# ui_ux.net
KiCad netlist of a schematic drawn in Altium Designer
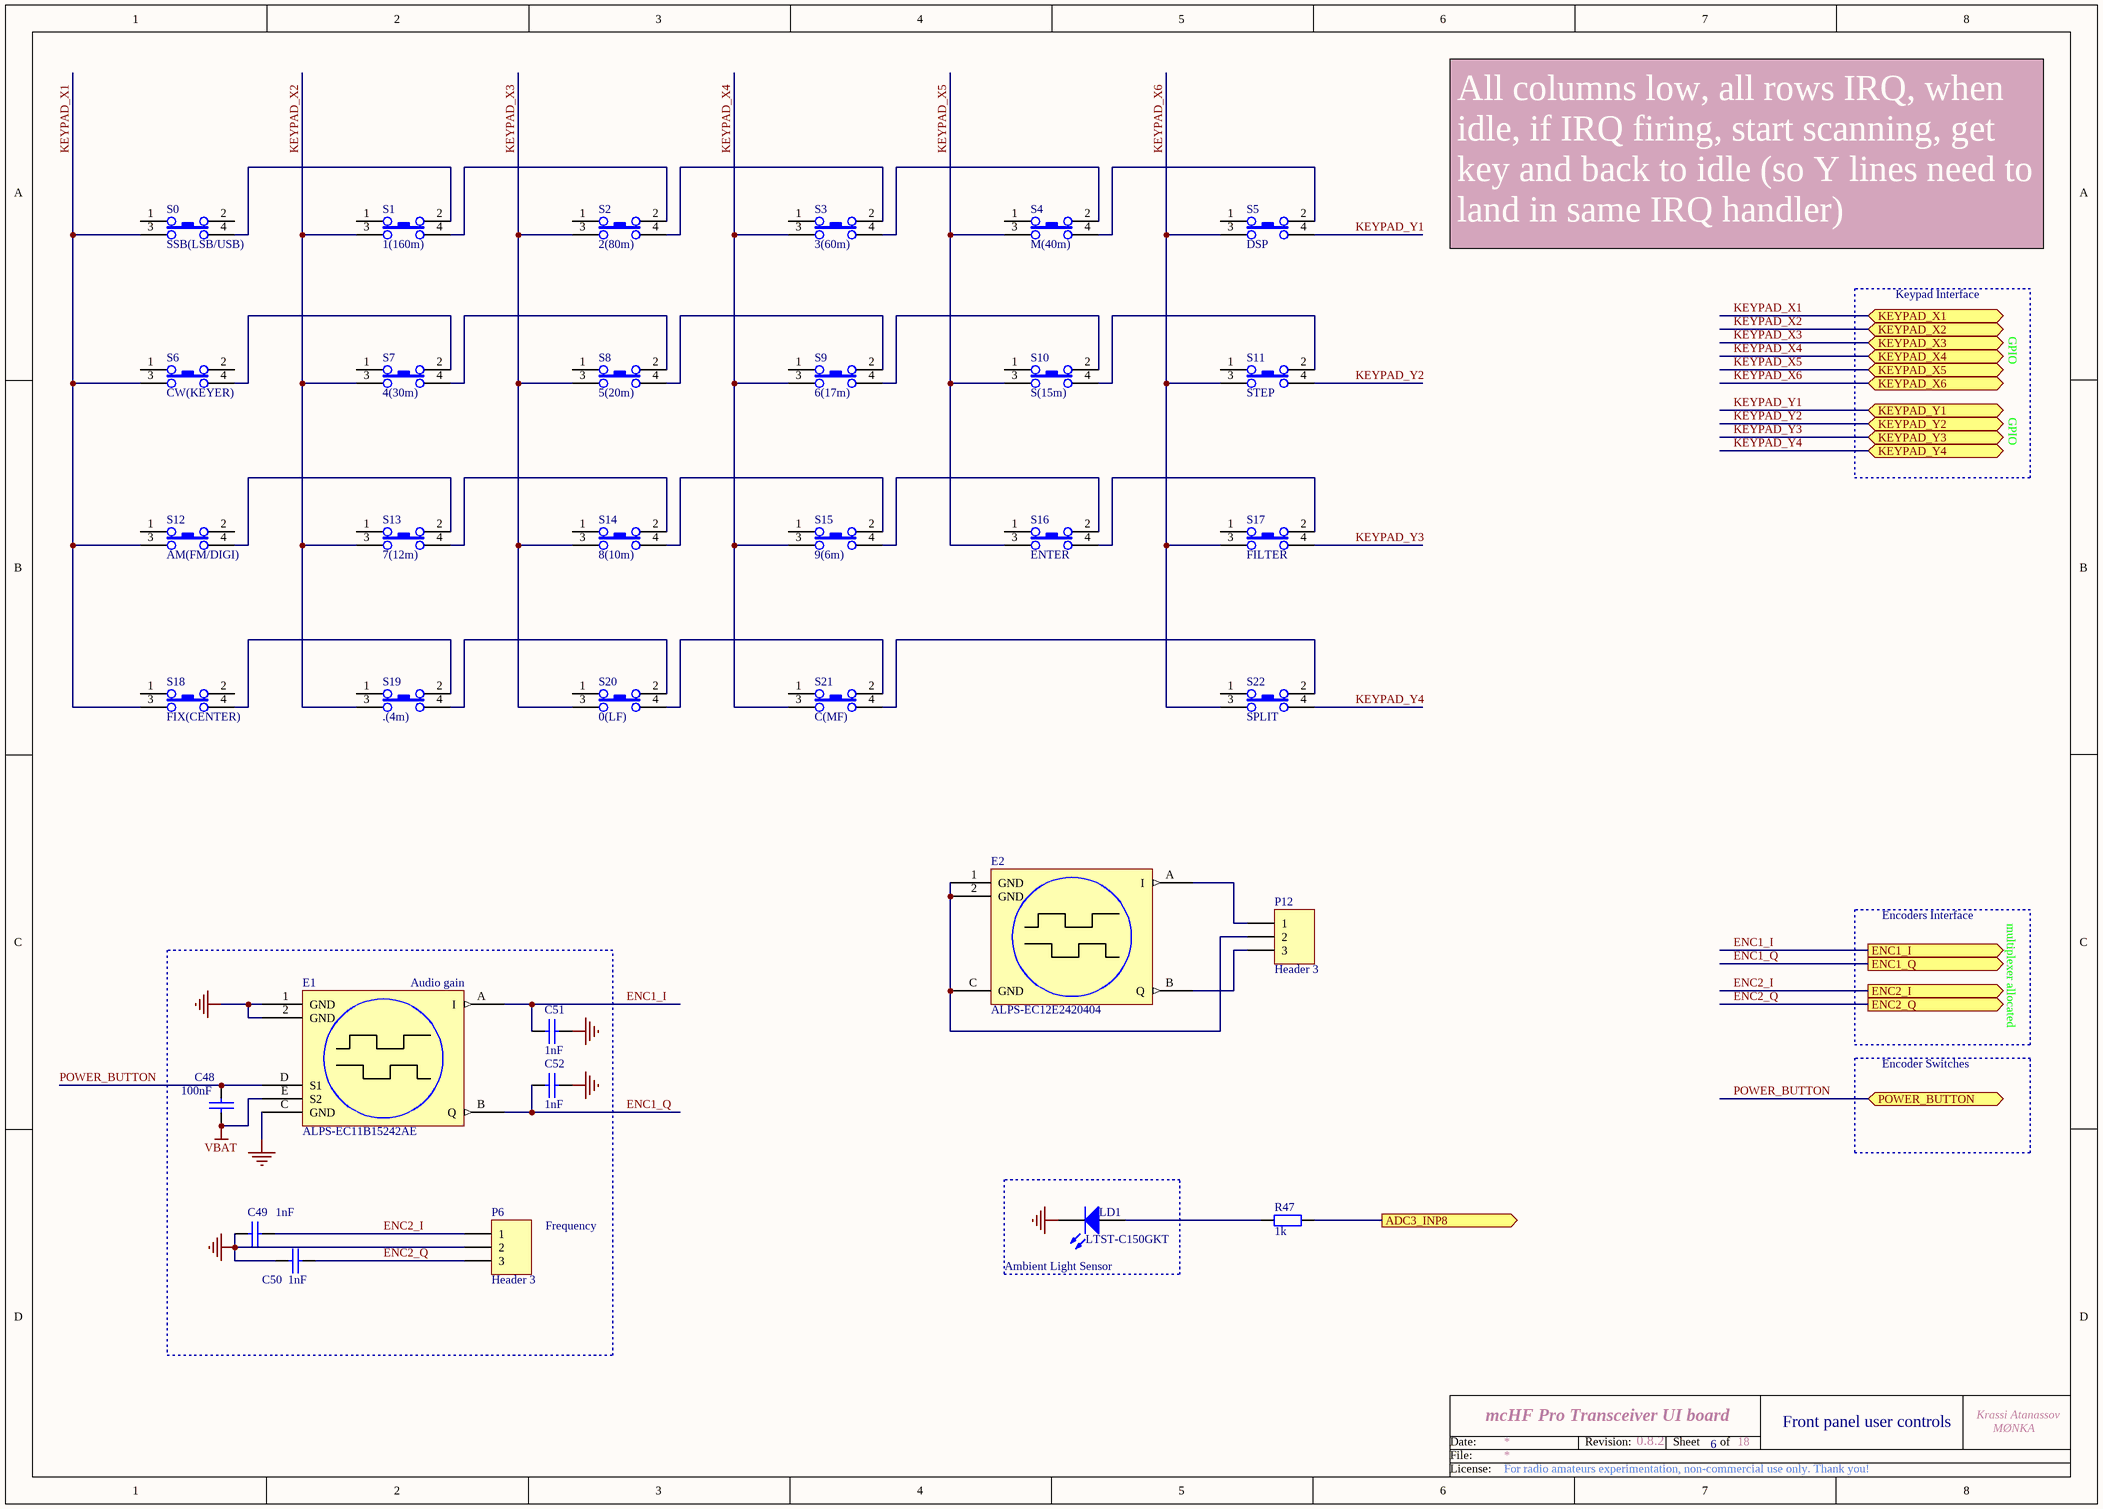
[diagram p0: ui_ux.SchDoc]

(export (version "E")
  (design (tool "Eeschema 10.0.6"))
  (components
    (comp (ref "C48")
      (value "100nF")
      (footprint "0805")
      (description "Capacitor")
      (libsource (lib "mcHF_ui") (part "CAP"))
    )
    (comp (ref "C49")
      (value "1nF")
      (footprint "0805")
      (description "Capacitor")
      (libsource (lib "mcHF_ui") (part "CAP"))
    )
    (comp (ref "C50")
      (value "1nF")
      (footprint "0805")
      (description "Capacitor")
      (libsource (lib "mcHF_ui") (part "CAP"))
    )
    (comp (ref "C51")
      (value "1nF")
      (footprint "0805")
      (description "Capacitor")
      (libsource (lib "mcHF_ui") (part "CAP"))
    )
    (comp (ref "C52")
      (value "1nF")
      (footprint "0805")
      (description "Capacitor")
      (libsource (lib "mcHF_ui") (part "CAP"))
    )
    (comp (ref "E1")
      (value "ALPS-EC11B15242AE")
      (footprint "EC11B_Horiz")
      (description "Horizontal Encoder")
      (libsource (lib "__ui") (part "EC11B_H"))
    )
    (comp (ref "E2")
      (value "ALPS-EC12E2420404")
      (footprint "Encoder")
      (description "ALPS Rotary Encoder")
      (libsource (lib "__ui") (part "Encoder"))
    )
    (comp (ref "LD1")
      (value "LTST-C150GKT")
      (footprint "1206_Elec_Cap")
      (description "LED 3mm")
      (libsource (lib "mcHF_ui") (part "LED2"))
    )
    (comp (ref "P6")
      (value "Header 3")
      (footprint "HDR1X3")
      (description "Header, 3-Pin")
      (libsource (lib "__ui") (part "Header 3"))
    )
    (comp (ref "P12")
      (value "Header 3")
      (footprint "HDR1X3")
      (description "Header, 3-Pin")
      (libsource (lib "__ui") (part "Header 3"))
    )
    (comp (ref "R47")
      (value "1k")
      (footprint "0805")
      (description "Resistor")
      (libsource (lib "mcHF_ui") (part "RES"))
    )
    (comp (ref "S0")
      (value "SSB(LSB/USB)")
      (footprint "BUTTON_SMD2")
      (description "Push Button")
      (libsource (lib "__ui") (part "SW-PB"))
    )
    (comp (ref "S1")
      (value "1(160m)")
      (footprint "BUTTON_SMD2")
      (description "Push Button")
      (libsource (lib "__ui") (part "SW-PB"))
    )
    (comp (ref "S2")
      (value "2(80m)")
      (footprint "BUTTON_SMD2")
      (description "Push Button")
      (libsource (lib "__ui") (part "SW-PB"))
    )
    (comp (ref "S3")
      (value "3(60m)")
      (footprint "BUTTON_SMD2")
      (description "Push Button")
      (libsource (lib "__ui") (part "SW-PB"))
    )
    (comp (ref "S4")
      (value "M(40m)")
      (footprint "BUTTON_SMD2")
      (description "Push Button")
      (libsource (lib "__ui") (part "SW-PB"))
    )
    (comp (ref "S5")
      (value "DSP")
      (footprint "BUTTON_SMD2")
      (description "Push Button")
      (libsource (lib "__ui") (part "SW-PB"))
    )
    (comp (ref "S6")
      (value "CW(KEYER)")
      (footprint "BUTTON_SMD2")
      (description "Push Button")
      (libsource (lib "__ui") (part "SW-PB"))
    )
    (comp (ref "S7")
      (value "4(30m)")
      (footprint "BUTTON_SMD2")
      (description "Push Button")
      (libsource (lib "__ui") (part "SW-PB"))
    )
    (comp (ref "S8")
      (value "5(20m)")
      (footprint "BUTTON_SMD2")
      (description "Push Button")
      (libsource (lib "__ui") (part "SW-PB"))
    )
    (comp (ref "S9")
      (value "6(17m)")
      (footprint "BUTTON_SMD2")
      (description "Push Button")
      (libsource (lib "__ui") (part "SW-PB"))
    )
    (comp (ref "S10")
      (value "S(15m)")
      (footprint "BUTTON_SMD2")
      (description "Push Button")
      (libsource (lib "__ui") (part "SW-PB"))
    )
    (comp (ref "S11")
      (value "STEP")
      (footprint "BUTTON_SMD2")
      (description "Push Button")
      (libsource (lib "__ui") (part "SW-PB"))
    )
    (comp (ref "S12")
      (value "AM(FM/DIGI)")
      (footprint "BUTTON_SMD2")
      (description "Push Button")
      (libsource (lib "__ui") (part "SW-PB"))
    )
    (comp (ref "S13")
      (value "7(12m)")
      (footprint "BUTTON_SMD2")
      (description "Push Button")
      (libsource (lib "__ui") (part "SW-PB"))
    )
    (comp (ref "S14")
      (value "8(10m)")
      (footprint "BUTTON_SMD2")
      (description "Push Button")
      (libsource (lib "__ui") (part "SW-PB"))
    )
    (comp (ref "S15")
      (value "9(6m)")
      (footprint "BUTTON_SMD2")
      (description "Push Button")
      (libsource (lib "__ui") (part "SW-PB"))
    )
    (comp (ref "S16")
      (value "ENTER")
      (footprint "BUTTON_SMD2")
      (description "Push Button")
      (libsource (lib "__ui") (part "SW-PB"))
    )
    (comp (ref "S17")
      (value "FILTER")
      (footprint "BUTTON_SMD2")
      (description "Push Button")
      (libsource (lib "__ui") (part "SW-PB"))
    )
    (comp (ref "S18")
      (value "FIX(CENTER)")
      (footprint "BUTTON_SMD2")
      (description "Push Button")
      (libsource (lib "__ui") (part "SW-PB"))
    )
    (comp (ref "S19")
      (value ".(4m)")
      (footprint "BUTTON_SMD2")
      (description "Push Button")
      (libsource (lib "__ui") (part "SW-PB"))
    )
    (comp (ref "S20")
      (value "0(LF)")
      (footprint "BUTTON_SMD2")
      (description "Push Button")
      (libsource (lib "__ui") (part "SW-PB"))
    )
    (comp (ref "S21")
      (value "C(MF)")
      (footprint "BUTTON_SMD2")
      (description "Push Button")
      (libsource (lib "__ui") (part "SW-PB"))
    )
    (comp (ref "S22")
      (value "SPLIT")
      (footprint "BUTTON_SMD2")
      (description "Push Button")
      (libsource (lib "__ui") (part "SW-PB"))
    )
  )
  (nets
    (net (code "1") (name "/ADC3_INP8") (class "Default")
      (node (ref "R47") (pin "1") (pinfunction "1_1") (pintype "passive"))
    )
    (net (code "2") (name "/ENC1_I") (class "Default")
      (node (ref "C51") (pin "1") (pinfunction "1_1") (pintype "passive"))
      (node (ref "E1") (pin "A") (pinfunction "I_A") (pintype "output"))
    )
    (net (code "3") (name "/ENC1_Q") (class "Default")
      (node (ref "C52") (pin "1") (pinfunction "1_1") (pintype "passive"))
      (node (ref "E1") (pin "B") (pinfunction "Q_B") (pintype "output"))
    )
    (net (code "4") (name "/ENC2_I") (class "Default")
      (node (ref "C49") (pin "1") (pinfunction "1_1") (pintype "passive"))
      (node (ref "P6") (pin "1") (pinfunction "1_1") (pintype "passive"))
    )
    (net (code "5") (name "/ENC2_Q") (class "Default")
      (node (ref "C50") (pin "1") (pinfunction "1_1") (pintype "passive"))
      (node (ref "P6") (pin "3") (pinfunction "3_3") (pintype "passive"))
    )
    (net (code "6") (name "/KEYPAD_X1") (class "Default")
      (node (ref "S0") (pin "3") (pinfunction "3_3") (pintype "passive"))
      (node (ref "S12") (pin "3") (pinfunction "3_3") (pintype "passive"))
      (node (ref "S18") (pin "3") (pinfunction "3_3") (pintype "passive"))
      (node (ref "S6") (pin "3") (pinfunction "3_3") (pintype "passive"))
    )
    (net (code "7") (name "/KEYPAD_X2") (class "Default")
      (node (ref "S1") (pin "3") (pinfunction "3_3") (pintype "passive"))
      (node (ref "S13") (pin "3") (pinfunction "3_3") (pintype "passive"))
      (node (ref "S19") (pin "3") (pinfunction "3_3") (pintype "passive"))
      (node (ref "S7") (pin "3") (pinfunction "3_3") (pintype "passive"))
    )
    (net (code "8") (name "/KEYPAD_X3") (class "Default")
      (node (ref "S14") (pin "3") (pinfunction "3_3") (pintype "passive"))
      (node (ref "S2") (pin "3") (pinfunction "3_3") (pintype "passive"))
      (node (ref "S20") (pin "3") (pinfunction "3_3") (pintype "passive"))
      (node (ref "S8") (pin "3") (pinfunction "3_3") (pintype "passive"))
    )
    (net (code "9") (name "/KEYPAD_X4") (class "Default")
      (node (ref "S15") (pin "3") (pinfunction "3_3") (pintype "passive"))
      (node (ref "S21") (pin "3") (pinfunction "3_3") (pintype "passive"))
      (node (ref "S3") (pin "3") (pinfunction "3_3") (pintype "passive"))
      (node (ref "S9") (pin "3") (pinfunction "3_3") (pintype "passive"))
    )
    (net (code "10") (name "/KEYPAD_X5") (class "Default")
      (node (ref "S10") (pin "3") (pinfunction "3_3") (pintype "passive"))
      (node (ref "S16") (pin "3") (pinfunction "3_3") (pintype "passive"))
      (node (ref "S4") (pin "3") (pinfunction "3_3") (pintype "passive"))
    )
    (net (code "11") (name "/KEYPAD_X6") (class "Default")
      (node (ref "S11") (pin "3") (pinfunction "3_3") (pintype "passive"))
      (node (ref "S17") (pin "3") (pinfunction "3_3") (pintype "passive"))
      (node (ref "S22") (pin "3") (pinfunction "3_3") (pintype "passive"))
      (node (ref "S5") (pin "3") (pinfunction "3_3") (pintype "passive"))
    )
    (net (code "12") (name "/KEYPAD_Y1") (class "Default")
      (node (ref "S5") (pin "4") (pinfunction "4_4") (pintype "passive"))
    )
    (net (code "13") (name "/KEYPAD_Y2") (class "Default")
      (node (ref "S11") (pin "4") (pinfunction "4_4") (pintype "passive"))
    )
    (net (code "14") (name "/KEYPAD_Y3") (class "Default")
      (node (ref "S17") (pin "4") (pinfunction "4_4") (pintype "passive"))
    )
    (net (code "15") (name "/KEYPAD_Y4") (class "Default")
      (node (ref "S22") (pin "4") (pinfunction "4_4") (pintype "passive"))
    )
    (net (code "16") (name "/POWER_BUTTON") (class "Default")
      (node (ref "C48") (pin "2") (pinfunction "2_2") (pintype "passive"))
      (node (ref "E1") (pin "D") (pinfunction "S1_D") (pintype "passive"))
    )
    (net (code "17") (name "GND") (class "Default")
      (node (ref "C49") (pin "2") (pinfunction "2_2") (pintype "passive"))
      (node (ref "C50") (pin "2") (pinfunction "2_2") (pintype "passive"))
      (node (ref "C51") (pin "2") (pinfunction "2_2") (pintype "passive"))
      (node (ref "C52") (pin "2") (pinfunction "2_2") (pintype "passive"))
      (node (ref "E1") (pin "1") (pinfunction "GND_1") (pintype "power_in"))
      (node (ref "E1") (pin "2") (pinfunction "GND_2") (pintype "power_in"))
      (node (ref "E1") (pin "C") (pinfunction "GND_C") (pintype "power_in"))
      (node (ref "LD1") (pin "2") (pinfunction "K_2") (pintype "passive"))
      (node (ref "P6") (pin "2") (pinfunction "2_2") (pintype "passive"))
    )
    (net (code "18") (name "Net-(E2-GND-Pad1)") (class "Default")
      (node (ref "E2") (pin "1") (pinfunction "GND_1") (pintype "power_in"))
      (node (ref "E2") (pin "2") (pinfunction "GND_2") (pintype "power_in"))
      (node (ref "E2") (pin "C") (pinfunction "GND_C") (pintype "power_in"))
      (node (ref "P12") (pin "2") (pinfunction "2_2") (pintype "passive"))
    )
    (net (code "19") (name "Net-(E2-I)") (class "Default")
      (node (ref "E2") (pin "A") (pinfunction "I_A") (pintype "output"))
      (node (ref "P12") (pin "1") (pinfunction "1_1") (pintype "passive"))
    )
    (net (code "20") (name "Net-(E2-Q)") (class "Default")
      (node (ref "E2") (pin "B") (pinfunction "Q_B") (pintype "output"))
      (node (ref "P12") (pin "3") (pinfunction "3_3") (pintype "passive"))
    )
    (net (code "21") (name "Net-(LD1-A)") (class "Default")
      (node (ref "LD1") (pin "1") (pinfunction "A_1") (pintype "passive"))
      (node (ref "R47") (pin "2") (pinfunction "2_2") (pintype "passive"))
    )
    (net (code "22") (name "Net-(S0-Pad4)") (class "Default")
      (node (ref "S0") (pin "4") (pinfunction "4_4") (pintype "passive"))
      (node (ref "S1") (pin "2") (pinfunction "2_2") (pintype "passive"))
    )
    (net (code "23") (name "Net-(S1-Pad4)") (class "Default")
      (node (ref "S1") (pin "4") (pinfunction "4_4") (pintype "passive"))
      (node (ref "S2") (pin "2") (pinfunction "2_2") (pintype "passive"))
    )
    (net (code "24") (name "Net-(S2-Pad4)") (class "Default")
      (node (ref "S2") (pin "4") (pinfunction "4_4") (pintype "passive"))
      (node (ref "S3") (pin "2") (pinfunction "2_2") (pintype "passive"))
    )
    (net (code "25") (name "Net-(S3-Pad4)") (class "Default")
      (node (ref "S3") (pin "4") (pinfunction "4_4") (pintype "passive"))
      (node (ref "S4") (pin "2") (pinfunction "2_2") (pintype "passive"))
    )
    (net (code "26") (name "Net-(S4-Pad4)") (class "Default")
      (node (ref "S4") (pin "4") (pinfunction "4_4") (pintype "passive"))
      (node (ref "S5") (pin "2") (pinfunction "2_2") (pintype "passive"))
    )
    (net (code "27") (name "Net-(S6-Pad4)") (class "Default")
      (node (ref "S6") (pin "4") (pinfunction "4_4") (pintype "passive"))
      (node (ref "S7") (pin "2") (pinfunction "2_2") (pintype "passive"))
    )
    (net (code "28") (name "Net-(S7-Pad4)") (class "Default")
      (node (ref "S7") (pin "4") (pinfunction "4_4") (pintype "passive"))
      (node (ref "S8") (pin "2") (pinfunction "2_2") (pintype "passive"))
    )
    (net (code "29") (name "Net-(S8-Pad4)") (class "Default")
      (node (ref "S8") (pin "4") (pinfunction "4_4") (pintype "passive"))
      (node (ref "S9") (pin "2") (pinfunction "2_2") (pintype "passive"))
    )
    (net (code "30") (name "Net-(S10-Pad2)") (class "Default")
      (node (ref "S10") (pin "2") (pinfunction "2_2") (pintype "passive"))
      (node (ref "S9") (pin "4") (pinfunction "4_4") (pintype "passive"))
    )
    (net (code "31") (name "Net-(S10-Pad4)") (class "Default")
      (node (ref "S10") (pin "4") (pinfunction "4_4") (pintype "passive"))
      (node (ref "S11") (pin "2") (pinfunction "2_2") (pintype "passive"))
    )
    (net (code "32") (name "Net-(S12-Pad4)") (class "Default")
      (node (ref "S12") (pin "4") (pinfunction "4_4") (pintype "passive"))
      (node (ref "S13") (pin "2") (pinfunction "2_2") (pintype "passive"))
    )
    (net (code "33") (name "Net-(S13-Pad4)") (class "Default")
      (node (ref "S13") (pin "4") (pinfunction "4_4") (pintype "passive"))
      (node (ref "S14") (pin "2") (pinfunction "2_2") (pintype "passive"))
    )
    (net (code "34") (name "Net-(S14-Pad4)") (class "Default")
      (node (ref "S14") (pin "4") (pinfunction "4_4") (pintype "passive"))
      (node (ref "S15") (pin "2") (pinfunction "2_2") (pintype "passive"))
    )
    (net (code "35") (name "Net-(S15-Pad4)") (class "Default")
      (node (ref "S15") (pin "4") (pinfunction "4_4") (pintype "passive"))
      (node (ref "S16") (pin "2") (pinfunction "2_2") (pintype "passive"))
    )
    (net (code "36") (name "Net-(S16-Pad4)") (class "Default")
      (node (ref "S16") (pin "4") (pinfunction "4_4") (pintype "passive"))
      (node (ref "S17") (pin "2") (pinfunction "2_2") (pintype "passive"))
    )
    (net (code "37") (name "Net-(S18-Pad4)") (class "Default")
      (node (ref "S18") (pin "4") (pinfunction "4_4") (pintype "passive"))
      (node (ref "S19") (pin "2") (pinfunction "2_2") (pintype "passive"))
    )
    (net (code "38") (name "Net-(S19-Pad4)") (class "Default")
      (node (ref "S19") (pin "4") (pinfunction "4_4") (pintype "passive"))
      (node (ref "S20") (pin "2") (pinfunction "2_2") (pintype "passive"))
    )
    (net (code "39") (name "Net-(S20-Pad4)") (class "Default")
      (node (ref "S20") (pin "4") (pinfunction "4_4") (pintype "passive"))
      (node (ref "S21") (pin "2") (pinfunction "2_2") (pintype "passive"))
    )
    (net (code "40") (name "Net-(S21-Pad4)") (class "Default")
      (node (ref "S21") (pin "4") (pinfunction "4_4") (pintype "passive"))
      (node (ref "S22") (pin "2") (pinfunction "2_2") (pintype "passive"))
    )
    (net (code "41") (name "VBAT") (class "Default")
      (node (ref "C48") (pin "1") (pinfunction "1_1") (pintype "passive"))
      (node (ref "E1") (pin "E") (pinfunction "S2_E") (pintype "passive"))
    )
    (net (code "42") (name "unconnected-(S0-Pad1)") (class "Default")
      (node (ref "S0") (pin "1") (pinfunction "1_1") (pintype "passive"))
    )
    (net (code "43") (name "unconnected-(S0-Pad2)") (class "Default")
      (node (ref "S0") (pin "2") (pinfunction "2_2") (pintype "passive"))
    )
    (net (code "44") (name "unconnected-(S1-Pad1)") (class "Default")
      (node (ref "S1") (pin "1") (pinfunction "1_1") (pintype "passive"))
    )
    (net (code "45") (name "unconnected-(S2-Pad1)") (class "Default")
      (node (ref "S2") (pin "1") (pinfunction "1_1") (pintype "passive"))
    )
    (net (code "46") (name "unconnected-(S3-Pad1)") (class "Default")
      (node (ref "S3") (pin "1") (pinfunction "1_1") (pintype "passive"))
    )
    (net (code "47") (name "unconnected-(S4-Pad1)") (class "Default")
      (node (ref "S4") (pin "1") (pinfunction "1_1") (pintype "passive"))
    )
    (net (code "48") (name "unconnected-(S5-Pad1)") (class "Default")
      (node (ref "S5") (pin "1") (pinfunction "1_1") (pintype "passive"))
    )
    (net (code "49") (name "unconnected-(S6-Pad1)") (class "Default")
      (node (ref "S6") (pin "1") (pinfunction "1_1") (pintype "passive"))
    )
    (net (code "50") (name "unconnected-(S6-Pad2)") (class "Default")
      (node (ref "S6") (pin "2") (pinfunction "2_2") (pintype "passive"))
    )
    (net (code "51") (name "unconnected-(S7-Pad1)") (class "Default")
      (node (ref "S7") (pin "1") (pinfunction "1_1") (pintype "passive"))
    )
    (net (code "52") (name "unconnected-(S8-Pad1)") (class "Default")
      (node (ref "S8") (pin "1") (pinfunction "1_1") (pintype "passive"))
    )
    (net (code "53") (name "unconnected-(S9-Pad1)") (class "Default")
      (node (ref "S9") (pin "1") (pinfunction "1_1") (pintype "passive"))
    )
    (net (code "54") (name "unconnected-(S10-Pad1)") (class "Default")
      (node (ref "S10") (pin "1") (pinfunction "1_1") (pintype "passive"))
    )
    (net (code "55") (name "unconnected-(S11-Pad1)") (class "Default")
      (node (ref "S11") (pin "1") (pinfunction "1_1") (pintype "passive"))
    )
    (net (code "56") (name "unconnected-(S12-Pad1)") (class "Default")
      (node (ref "S12") (pin "1") (pinfunction "1_1") (pintype "passive"))
    )
    (net (code "57") (name "unconnected-(S12-Pad2)") (class "Default")
      (node (ref "S12") (pin "2") (pinfunction "2_2") (pintype "passive"))
    )
    (net (code "58") (name "unconnected-(S13-Pad1)") (class "Default")
      (node (ref "S13") (pin "1") (pinfunction "1_1") (pintype "passive"))
    )
    (net (code "59") (name "unconnected-(S14-Pad1)") (class "Default")
      (node (ref "S14") (pin "1") (pinfunction "1_1") (pintype "passive"))
    )
    (net (code "60") (name "unconnected-(S15-Pad1)") (class "Default")
      (node (ref "S15") (pin "1") (pinfunction "1_1") (pintype "passive"))
    )
    (net (code "61") (name "unconnected-(S16-Pad1)") (class "Default")
      (node (ref "S16") (pin "1") (pinfunction "1_1") (pintype "passive"))
    )
    (net (code "62") (name "unconnected-(S17-Pad1)") (class "Default")
      (node (ref "S17") (pin "1") (pinfunction "1_1") (pintype "passive"))
    )
    (net (code "63") (name "unconnected-(S18-Pad1)") (class "Default")
      (node (ref "S18") (pin "1") (pinfunction "1_1") (pintype "passive"))
    )
    (net (code "64") (name "unconnected-(S18-Pad2)") (class "Default")
      (node (ref "S18") (pin "2") (pinfunction "2_2") (pintype "passive"))
    )
    (net (code "65") (name "unconnected-(S19-Pad1)") (class "Default")
      (node (ref "S19") (pin "1") (pinfunction "1_1") (pintype "passive"))
    )
    (net (code "66") (name "unconnected-(S20-Pad1)") (class "Default")
      (node (ref "S20") (pin "1") (pinfunction "1_1") (pintype "passive"))
    )
    (net (code "67") (name "unconnected-(S21-Pad1)") (class "Default")
      (node (ref "S21") (pin "1") (pinfunction "1_1") (pintype "passive"))
    )
    (net (code "68") (name "unconnected-(S22-Pad1)") (class "Default")
      (node (ref "S22") (pin "1") (pinfunction "1_1") (pintype "passive"))
    )
  )
)
